# Transmitter.net
KiCad netlist of a schematic drawn in Altium Designer
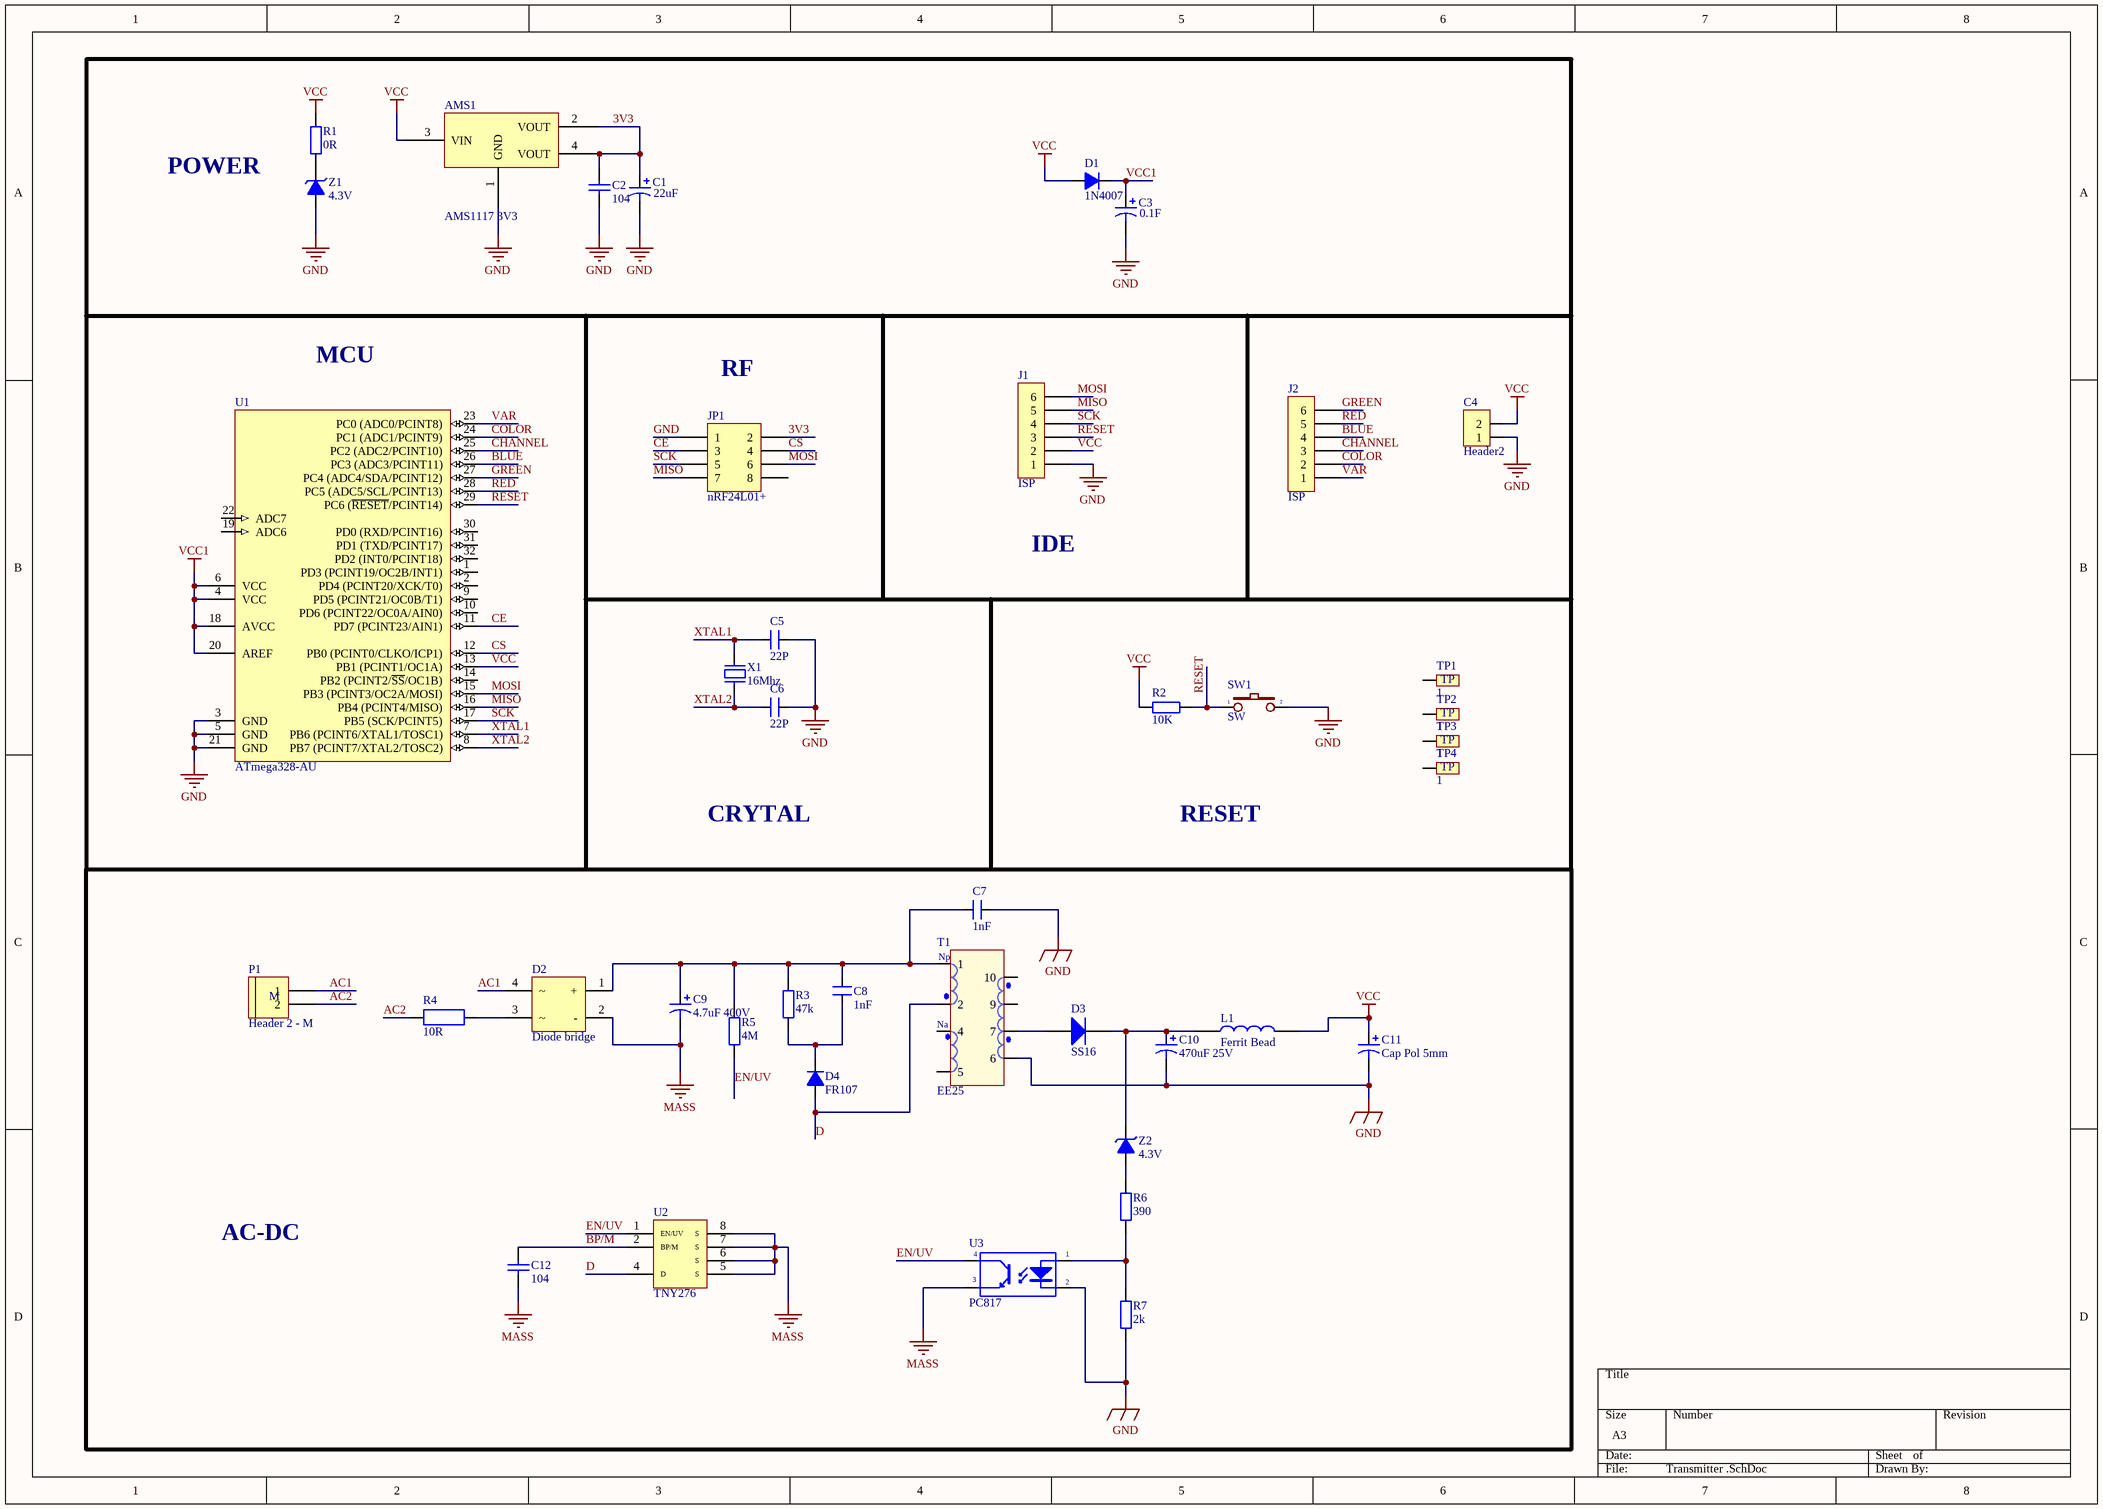
[diagram p0: Transmitter .SchDoc]

(export (version "E")
  (design (tool "Eeschema 10.0.6"))
  (components
    (comp (ref "AMS1")
      (value "AMS1117 3V3")
      (footprint "SOT223-4N")
      (description "AMS")
      (libsource (lib "Thu Vien Chuan") (part "AMS1117"))
    )
    (comp (ref "C1")
      (value "22uF")
      (footprint "C5mm")
      (description "Polarized Capacitor (Axial)")
      (fields (field (name "PUBLISHER") "Altium Limited"))
      (libsource (lib "Thu Vien Chuan") (part "Cap Pol 5mm"))
    )
    (comp (ref "C2")
      (value "104")
      (footprint "Thu Vien Chuan :CN-SMD-0805")
      (libsource (lib "Thu Vien Chuan") (part "CAP 33P_0805"))
    )
    (comp (ref "C3")
      (value "0.1F")
      (footprint "HueNguyenLib:SUP CAP")
      (description "Polarized Capacitor (Axial)")
      (fields (field (name "PUBLISHER") "Altium Limited"))
      (libsource (lib "Thu Vien Chuan") (part "Cap Pol 5mm"))
    )
    (comp (ref "C4")
      (value "Header2")
      (footprint "HDR2")
      (description "Header IDC, 2 x 1 Pin Vertical 2.54mm Pitch (Non-Boxed, Male)")
      (fields
        (field (name "MANUFACTURER") "Würth Elektronik eiSos GmbH")
        (field (name "PARTNO") "613002143121")
        (field (name "CREATED BY") "Karrer Zheng")
      )
      (libsource (lib "Thu Vien Chuan") (part "Header2"))
    )
    (comp (ref "C5")
      (value "22P")
      (footprint "Thu Vien Chuan :CN-SMD-0805")
      (description "Cap np  1pF - 472pF")
      (libsource (lib "Thu Vien Chuan") (part "CN1"))
    )
    (comp (ref "C6")
      (value "22P")
      (footprint "Thu Vien Chuan :CN-SMD-0805")
      (description "Cap np  1pF - 472pF")
      (libsource (lib "Thu Vien Chuan") (part "CN1"))
    )
    (comp (ref "C7")
      (value "1nF")
      (footprint "Thu Vien Chuan :CN4")
      (description "Cap np W0.3")
      (fields (field (name "COPYRIGHT") "VanDungEvn"))
      (libsource (lib "Thu Vien Chuan") (part "CN3"))
    )
    (comp (ref "C8")
      (value "1nF")
      (footprint "CN2")
      (description "Cap np 104 => 105pF")
      (libsource (lib "Thu Vien Chuan") (part "CN2"))
    )
    (comp (ref "C9")
      (value "4.7uF 400V")
      (footprint "C10mm")
      (description "Polarized Capacitor (Axial)")
      (fields (field (name "PUBLISHER") "Altium Limited"))
      (libsource (lib "Thu Vien Chuan") (part "Cap Pol 8mm"))
    )
    (comp (ref "C10")
      (value "470uF 25V")
      (footprint "C10mm")
      (description "Polarized Capacitor (Axial)")
      (fields (field (name "PUBLISHER") "Altium Limited"))
      (libsource (lib "Thu Vien Chuan") (part "Cap Pol 8mm"))
    )
    (comp (ref "C11")
      (value "Cap Pol 5mm")
      (footprint "C5mm")
      (description "Polarized Capacitor (Axial)")
      (fields (field (name "PUBLISHER") "Altium Limited"))
      (libsource (lib "Thu Vien Chuan") (part "Cap Pol 5mm"))
    )
    (comp (ref "C12")
      (value "104")
      (footprint "Thu Vien Chuan :CN-SMD-0805")
      (libsource (lib "Thu Vien Chuan") (part "CAP 33P_0805"))
    )
    (comp (ref "D1")
      (value "1N4007")
      (footprint "D1A")
      (description "Diode 1A")
      (libsource (lib "Thu Vien Chuan") (part "D1A"))
    )
    (comp (ref "D2")
      (value "Diode bridge")
      (footprint "DS207S:DS207S")
      (description "Diode cau 2A 1000V")
      (libsource (lib "DS207S") (part "DS207S"))
    )
    (comp (ref "D3")
      (value "SS16")
      (footprint "HueNguyenLib:SS14")
      (description "Dán")
      (libsource (lib "Altium_Lib_by_KhueNguyenCreator") (part "Diode SS14 ( 1N5819)"))
    )
    (comp (ref "D4")
      (value "FR107")
      (footprint "D1A")
      (description "Diode 1A")
      (libsource (lib "Thu Vien Chuan") (part "D1A"))
    )
    (comp (ref "J1")
      (value "ISP")
      (footprint "Thu Vien Chuan :Header6")
      (description "JUMP DON DUC 2.54")
      (libsource (lib "Thu Vien Chuan") (part "JUMP 6"))
    )
    (comp (ref "J2")
      (value "ISP")
      (footprint "Thu Vien Chuan :Header6")
      (description "JUMP DON DUC 2.54")
      (libsource (lib "Thu Vien Chuan") (part "JUMP 6"))
    )
    (comp (ref "JP1")
      (value "nRF24L01+")
      (footprint "HDR2X4")
      (description "JUMP DOI DUC")
      (fields (field (name "PUBLISHER") "Altium Limited"))
      (libsource (lib "Thu Vien Chuan") (part "JUMP DOI-4"))
    )
    (comp (ref "L1")
      (value "Ferrit Bead")
      (footprint "Cuon Cam:CUON CAM")
      (description "Cuộn lọc RH3.5x9x0.8 Cắm")
      (libsource (lib "Altium_Lib_by_KhueNguyenCreator") (part "CUON CAM 470uH DIP"))
    )
    (comp (ref "P1")
      (value "Header 2 - M")
      (footprint "Medium - Header 2")
      (description "Header, 2-Pin, Medium")
      (fields (field (name "PUBLISHER") "Altium Limited"))
      (libsource (lib "Thu Vien Chuan") (part "Header 2 - M"))
    )
    (comp (ref "R1")
      (value "0R")
      (footprint "Thu Vien Chuan :1206_R")
      (description "Resistor 1/4W")
      (libsource (lib "Thu Vien Chuan") (part "R1/4W"))
    )
    (comp (ref "R2")
      (value "10K")
      (footprint "Thu Vien Chuan :RES-SMD-0805")
      (description "Resistor 1/4W")
      (libsource (lib "Thu Vien Chuan") (part "R1/4W"))
    )
    (comp (ref "R3")
      (value "47k")
      (footprint "Thu Vien Chuan :RES-SMD-0805")
      (description "Resistor 1/4W")
      (libsource (lib "Thu Vien Chuan") (part "R1/4W"))
    )
    (comp (ref "R4")
      (value "10R")
      (footprint "Thu Vien Chuan :RES-1W-LONG")
      (description "Resistor 1W")
      (libsource (lib "Thu Vien Chuan") (part "R1W"))
    )
    (comp (ref "R5")
      (value "4M")
      (footprint "Thu Vien Chuan :RES-SMD-0805")
      (description "Resistor 1/4W")
      (libsource (lib "Thu Vien Chuan") (part "R1/4W"))
    )
    (comp (ref "R6")
      (value "390")
      (footprint "Thu Vien Chuan :RES-SMD-0805")
      (description "Resistor 1/4W")
      (libsource (lib "Thu Vien Chuan") (part "R1/4W"))
    )
    (comp (ref "R7")
      (value "2k")
      (footprint "Thu Vien Chuan :RES-SMD-0805")
      (description "Resistor 1/4W")
      (libsource (lib "Thu Vien Chuan") (part "R1/4W"))
    )
    (comp (ref "SW1")
      (value "SW")
      (footprint "SW2")
      (description "Switch button 2 pin")
      (libsource (lib "Thu Vien Chuan") (part "SW2"))
    )
    (comp (ref "T1")
      (value "EE25")
      (footprint "HueNguyenLib:EE19 5+5")
      (description "EE25 10PIN")
      (libsource (lib "EE25") (part "EE25"))
    )
    (comp (ref "TP1")
      (value "1")
      (footprint "ThePhongLib:Holle 3mm 8mm")
      (description "CONNECT 1")
      (libsource (lib "Thu Vien Chuan MH") (part "TP"))
    )
    (comp (ref "TP2")
      (value "1")
      (footprint "ThePhongLib:Holle 3mm 8mm")
      (description "CONNECT 1")
      (libsource (lib "Thu Vien Chuan MH") (part "TP"))
    )
    (comp (ref "TP3")
      (value "1")
      (footprint "ThePhongLib:Holle 3mm 8mm")
      (description "CONNECT 1")
      (libsource (lib "Thu Vien Chuan MH") (part "TP"))
    )
    (comp (ref "TP4")
      (value "1")
      (footprint "ThePhongLib:Holle 3mm 8mm")
      (description "CONNECT 1")
      (libsource (lib "Thu Vien Chuan MH") (part "TP"))
    )
    (comp (ref "U1")
      (value "ATmega328-AU")
      (footprint "TQFP32")
      (fields (field (name "PUBLISHER") "Altium Limited"))
      (libsource (lib "Thu Vien Chuan") (part "ATmega328-AU"))
    )
    (comp (ref "U2")
      (value "TNY276")
      (footprint "TNY27X DIP:PCBComponent_1")
      (description "TNY274-280\r\nTinySwitch-III Family - DIP/PDIP-8C")
      (libsource (lib "TNY27X-DIP") (part "TNY276"))
    )
    (comp (ref "U3")
      (value "PC817")
      (footprint "DIP4/W0.3")
      (description "Single Opto")
      (libsource (lib "Thu Vien Chuan") (part "PC817"))
    )
    (comp (ref "X1")
      (value "16Mhz")
      (footprint "XT2")
      (description "Crystal For all Crystal 2pin.")
      (libsource (lib "Thu Vien Chuan") (part "XT2"))
    )
    (comp (ref "Z1")
      (value "4.3V")
      (footprint "D1A")
      (description "Diode  Zener")
      (libsource (lib "Thu Vien Chuan") (part "Diode Zener"))
    )
    (comp (ref "Z2")
      (value "4.3V")
      (footprint "D1A")
      (description "Diode  Zener")
      (libsource (lib "Thu Vien Chuan") (part "Diode Zener"))
    )
  )
  (nets
    (net (code "1") (name "/3V3") (class "Default")
      (node (ref "AMS1") (pin "2") (pinfunction "VOUT_2") (pintype "passive"))
      (node (ref "AMS1") (pin "4") (pinfunction "VOUT_4") (pintype "passive"))
      (node (ref "C1") (pin "1") (pinfunction "1_1") (pintype "passive"))
      (node (ref "C2") (pin "2") (pinfunction "2_2") (pintype "passive"))
      (node (ref "JP1") (pin "2") (pinfunction "2_2") (pintype "passive"))
    )
    (net (code "2") (name "/AC1") (class "Default")
      (node (ref "D2") (pin "4") (pinfunction "~_4") (pintype "passive"))
      (node (ref "P1") (pin "1") (pinfunction "1_1") (pintype "passive"))
    )
    (net (code "3") (name "/AC2") (class "Default")
      (node (ref "P1") (pin "2") (pinfunction "2_2") (pintype "passive"))
      (node (ref "R4") (pin "1") (pinfunction "1_1") (pintype "passive"))
    )
    (net (code "4") (name "/BLUE") (class "Default")
      (node (ref "J2") (pin "4") (pinfunction "4_4") (pintype "passive"))
      (node (ref "U1") (pin "26") (pinfunction "PC3_(ADC3/PCINT11)_26") (pintype "bidirectional"))
    )
    (net (code "5") (name "/BP{slash}M") (class "Default")
      (node (ref "C12") (pin "2") (pinfunction "2_2") (pintype "passive"))
      (node (ref "U2") (pin "2") (pinfunction "BP/M_2") (pintype "passive"))
    )
    (net (code "6") (name "/CE") (class "Default")
      (node (ref "JP1") (pin "3") (pinfunction "3_3") (pintype "passive"))
      (node (ref "U1") (pin "11") (pinfunction "PD7_(PCINT23/AIN1)_11") (pintype "bidirectional"))
    )
    (net (code "7") (name "/CHANNEL") (class "Default")
      (node (ref "J2") (pin "3") (pinfunction "3_3") (pintype "passive"))
      (node (ref "U1") (pin "25") (pinfunction "PC2_(ADC2/PCINT10)_25") (pintype "bidirectional"))
    )
    (net (code "8") (name "/COLOR") (class "Default")
      (node (ref "J2") (pin "2") (pinfunction "2_2") (pintype "passive"))
      (node (ref "U1") (pin "24") (pinfunction "PC1_(ADC1/PCINT9)_24") (pintype "bidirectional"))
    )
    (net (code "9") (name "/CS") (class "Default")
      (node (ref "JP1") (pin "4") (pinfunction "4_4") (pintype "passive"))
      (node (ref "U1") (pin "12") (pinfunction "PB0_(PCINT0/CLKO/ICP1)_12") (pintype "bidirectional"))
    )
    (net (code "10") (name "/D") (class "Default")
      (node (ref "D4") (pin "1") (pinfunction "A_1") (pintype "passive"))
      (node (ref "T1") (pin "2") (pinfunction "2_2") (pintype "passive"))
      (node (ref "U2") (pin "4") (pinfunction "D_4") (pintype "passive"))
    )
    (net (code "11") (name "/EN{slash}UV") (class "Default")
      (node (ref "R5") (pin "1") (pinfunction "1_1") (pintype "passive"))
      (node (ref "U2") (pin "1") (pinfunction "EN/UV_1") (pintype "passive"))
      (node (ref "U3") (pin "4") (pinfunction "C_4") (pintype "passive"))
    )
    (net (code "12") (name "/GREEN") (class "Default")
      (node (ref "J2") (pin "6") (pinfunction "6_6") (pintype "passive"))
      (node (ref "U1") (pin "27") (pinfunction "PC4_(ADC4/SDA/PCINT12)_27") (pintype "bidirectional"))
    )
    (net (code "13") (name "/MISO") (class "Default")
      (node (ref "J1") (pin "5") (pinfunction "5_5") (pintype "passive"))
      (node (ref "JP1") (pin "7") (pinfunction "7_7") (pintype "passive"))
      (node (ref "U1") (pin "16") (pinfunction "PB4_(PCINT4/MISO)_16") (pintype "bidirectional"))
    )
    (net (code "14") (name "/MOSI") (class "Default")
      (node (ref "J1") (pin "6") (pinfunction "6_6") (pintype "passive"))
      (node (ref "JP1") (pin "6") (pinfunction "6_6") (pintype "passive"))
      (node (ref "U1") (pin "15") (pinfunction "PB3_(PCINT3/OC2A/MOSI)_15") (pintype "bidirectional"))
    )
    (net (code "15") (name "/RED") (class "Default")
      (node (ref "J2") (pin "5") (pinfunction "5_5") (pintype "passive"))
      (node (ref "U1") (pin "28") (pinfunction "PC5_(ADC5/SCL/PCINT13)_28") (pintype "bidirectional"))
    )
    (net (code "16") (name "/RESET") (class "Default")
      (node (ref "J1") (pin "3") (pinfunction "3_3") (pintype "passive"))
      (node (ref "R2") (pin "2") (pinfunction "2_2") (pintype "passive"))
      (node (ref "SW1") (pin "1") (pinfunction "1_1") (pintype "passive"))
      (node (ref "U1") (pin "29") (pinfunction "PC6_(~{RESET}/PCINT14)_29") (pintype "bidirectional"))
    )
    (net (code "17") (name "/SCK") (class "Default")
      (node (ref "J1") (pin "4") (pinfunction "4_4") (pintype "passive"))
      (node (ref "JP1") (pin "5") (pinfunction "5_5") (pintype "passive"))
      (node (ref "U1") (pin "17") (pinfunction "PB5_(SCK/PCINT5)_17") (pintype "bidirectional"))
    )
    (net (code "18") (name "/VAR") (class "Default")
      (node (ref "J2") (pin "1") (pinfunction "1_1") (pintype "passive"))
      (node (ref "U1") (pin "23") (pinfunction "PC0_(ADC0/PCINT8)_23") (pintype "bidirectional"))
    )
    (net (code "19") (name "/XTAL1") (class "Default")
      (node (ref "C5") (pin "2") (pinfunction "2_2") (pintype "passive"))
      (node (ref "U1") (pin "7") (pinfunction "PB6_(PCINT6/XTAL1/TOSC1)_7") (pintype "bidirectional"))
      (node (ref "X1") (pin "2") (pinfunction "2_2") (pintype "passive"))
    )
    (net (code "20") (name "/XTAL2") (class "Default")
      (node (ref "C6") (pin "2") (pinfunction "2_2") (pintype "passive"))
      (node (ref "U1") (pin "8") (pinfunction "PB7_(PCINT7/XTAL2/TOSC2)_8") (pintype "bidirectional"))
      (node (ref "X1") (pin "1") (pinfunction "1_1") (pintype "passive"))
    )
    (net (code "21") (name "GND") (class "Default")
      (node (ref "AMS1") (pin "1") (pinfunction "GND_1") (pintype "passive"))
      (node (ref "C1") (pin "2") (pinfunction "2_2") (pintype "passive"))
      (node (ref "C10") (pin "2") (pinfunction "2_2") (pintype "passive"))
      (node (ref "C11") (pin "2") (pinfunction "2_2") (pintype "passive"))
      (node (ref "C2") (pin "1") (pinfunction "1_1") (pintype "passive"))
      (node (ref "C3") (pin "2") (pinfunction "2_2") (pintype "passive"))
      (node (ref "C4") (pin "1") (pinfunction "1_1") (pintype "passive"))
      (node (ref "C5") (pin "1") (pinfunction "1_1") (pintype "passive"))
      (node (ref "C6") (pin "1") (pinfunction "1_1") (pintype "passive"))
      (node (ref "C7") (pin "2") (pinfunction "2_2") (pintype "passive"))
      (node (ref "J1") (pin "1") (pinfunction "1_1") (pintype "passive"))
      (node (ref "JP1") (pin "1") (pinfunction "1_1") (pintype "passive"))
      (node (ref "R7") (pin "1") (pinfunction "1_1") (pintype "passive"))
      (node (ref "SW1") (pin "2") (pinfunction "2_2") (pintype "passive"))
      (node (ref "T1") (pin "6") (pinfunction "6_6") (pintype "passive"))
      (node (ref "U1") (pin "21") (pinfunction "GND_21") (pintype "power_in"))
      (node (ref "U1") (pin "3") (pinfunction "GND_3") (pintype "power_in"))
      (node (ref "U1") (pin "5") (pinfunction "GND_5") (pintype "power_in"))
      (node (ref "U3") (pin "2") (pinfunction "K_2") (pintype "passive"))
      (node (ref "Z1") (pin "1") (pinfunction "A_1") (pintype "passive"))
    )
    (net (code "22") (name "MASS") (class "Default")
      (node (ref "C12") (pin "1") (pinfunction "1_1") (pintype "passive"))
      (node (ref "C9") (pin "2") (pinfunction "2_2") (pintype "passive"))
      (node (ref "D2") (pin "2") (pinfunction "-_2") (pintype "passive"))
      (node (ref "U2") (pin "5") (pinfunction "S_5") (pintype "passive"))
      (node (ref "U2") (pin "6") (pinfunction "S_6") (pintype "passive"))
      (node (ref "U2") (pin "7") (pinfunction "S_7") (pintype "passive"))
      (node (ref "U2") (pin "8") (pinfunction "S_8") (pintype "passive"))
      (node (ref "U3") (pin "3") (pinfunction "E_3") (pintype "passive"))
    )
    (net (code "23") (name "Net-(D2-+)") (class "Default")
      (node (ref "C7") (pin "1") (pinfunction "1_1") (pintype "passive"))
      (node (ref "C8") (pin "2") (pinfunction "2_2") (pintype "passive"))
      (node (ref "C9") (pin "1") (pinfunction "1_1") (pintype "passive"))
      (node (ref "D2") (pin "1") (pinfunction "+_1") (pintype "passive"))
      (node (ref "R3") (pin "2") (pinfunction "2_2") (pintype "passive"))
      (node (ref "R5") (pin "2") (pinfunction "2_2") (pintype "passive"))
      (node (ref "T1") (pin "1") (pinfunction "1_1") (pintype "passive"))
    )
    (net (code "24") (name "Net-(D2-~-Pad3)") (class "Default")
      (node (ref "D2") (pin "3") (pinfunction "~_3") (pintype "passive"))
      (node (ref "R4") (pin "2") (pinfunction "2_2") (pintype "passive"))
    )
    (net (code "25") (name "Net-(D3-A)") (class "Default")
      (node (ref "D3") (pin "1") (pinfunction "A_1") (pintype "passive"))
      (node (ref "T1") (pin "7") (pinfunction "7_7") (pintype "passive"))
    )
    (net (code "26") (name "Net-(D3-K)") (class "Default")
      (node (ref "C10") (pin "1") (pinfunction "1_1") (pintype "passive"))
      (node (ref "D3") (pin "2") (pinfunction "K_2") (pintype "passive"))
      (node (ref "L1") (pin "1") (pinfunction "1_1") (pintype "passive"))
      (node (ref "Z2") (pin "2") (pinfunction "K_2") (pintype "passive"))
    )
    (net (code "27") (name "Net-(D4-K)") (class "Default")
      (node (ref "C8") (pin "1") (pinfunction "1_1") (pintype "passive"))
      (node (ref "D4") (pin "2") (pinfunction "K_2") (pintype "passive"))
      (node (ref "R3") (pin "1") (pinfunction "1_1") (pintype "passive"))
    )
    (net (code "28") (name "Net-(U3-A)") (class "Default")
      (node (ref "R6") (pin "1") (pinfunction "1_1") (pintype "passive"))
      (node (ref "R7") (pin "2") (pinfunction "2_2") (pintype "passive"))
      (node (ref "U3") (pin "1") (pinfunction "A_1") (pintype "passive"))
    )
    (net (code "29") (name "Net-(Z1-K)") (class "Default")
      (node (ref "R1") (pin "1") (pinfunction "1_1") (pintype "passive"))
      (node (ref "Z1") (pin "2") (pinfunction "K_2") (pintype "passive"))
    )
    (net (code "30") (name "Net-(Z2-A)") (class "Default")
      (node (ref "R6") (pin "2") (pinfunction "2_2") (pintype "passive"))
      (node (ref "Z2") (pin "1") (pinfunction "A_1") (pintype "passive"))
    )
    (net (code "31") (name "VCC") (class "Default")
      (node (ref "AMS1") (pin "3") (pinfunction "VIN_3") (pintype "passive"))
      (node (ref "C11") (pin "1") (pinfunction "1_1") (pintype "passive"))
      (node (ref "C4") (pin "2") (pinfunction "2_2") (pintype "passive"))
      (node (ref "D1") (pin "1") (pinfunction "A_1") (pintype "passive"))
      (node (ref "J1") (pin "2") (pinfunction "2_2") (pintype "passive"))
      (node (ref "L1") (pin "2") (pinfunction "2_2") (pintype "passive"))
      (node (ref "R1") (pin "2") (pinfunction "2_2") (pintype "passive"))
      (node (ref "R2") (pin "1") (pinfunction "1_1") (pintype "passive"))
      (node (ref "U1") (pin "13") (pinfunction "PB1_(PCINT1/OC1A)_13") (pintype "bidirectional"))
    )
    (net (code "32") (name "VCC1") (class "Default")
      (node (ref "C3") (pin "1") (pinfunction "1_1") (pintype "passive"))
      (node (ref "D1") (pin "2") (pinfunction "K_2") (pintype "passive"))
      (node (ref "U1") (pin "18") (pinfunction "AVCC_18") (pintype "power_in"))
      (node (ref "U1") (pin "20") (pinfunction "AREF_20") (pintype "passive"))
      (node (ref "U1") (pin "4") (pinfunction "VCC_4") (pintype "power_in"))
      (node (ref "U1") (pin "6") (pinfunction "VCC_6") (pintype "power_in"))
    )
    (net (code "33") (name "unconnected-(JP1-Pad8)") (class "Default")
      (node (ref "JP1") (pin "8") (pinfunction "8_8") (pintype "passive"))
    )
    (net (code "34") (name "unconnected-(T1-Pad4)") (class "Default")
      (node (ref "T1") (pin "4") (pinfunction "4_4") (pintype "passive"))
    )
    (net (code "35") (name "unconnected-(T1-Pad5)") (class "Default")
      (node (ref "T1") (pin "5") (pinfunction "5_5") (pintype "passive"))
    )
    (net (code "36") (name "unconnected-(T1-Pad9)") (class "Default")
      (node (ref "T1") (pin "9") (pinfunction "9_9") (pintype "passive"))
    )
    (net (code "37") (name "unconnected-(T1-Pad10)") (class "Default")
      (node (ref "T1") (pin "10") (pinfunction "10_10") (pintype "passive"))
    )
    (net (code "38") (name "unconnected-(TP1-0-PadTP1)") (class "Default")
      (node (ref "TP1") (pin "TP1") (pinfunction "0_TP1") (pintype "passive"))
    )
    (net (code "39") (name "unconnected-(TP2-0-PadTP1)") (class "Default")
      (node (ref "TP2") (pin "TP1") (pinfunction "0_TP1") (pintype "passive"))
    )
    (net (code "40") (name "unconnected-(TP3-0-PadTP1)") (class "Default")
      (node (ref "TP3") (pin "TP1") (pinfunction "0_TP1") (pintype "passive"))
    )
    (net (code "41") (name "unconnected-(TP4-0-PadTP1)") (class "Default")
      (node (ref "TP4") (pin "TP1") (pinfunction "0_TP1") (pintype "passive"))
    )
    (net (code "42") (name "unconnected-(U1-ADC6-Pad19)") (class "Default")
      (node (ref "U1") (pin "19") (pinfunction "ADC6_19") (pintype "input"))
    )
    (net (code "43") (name "unconnected-(U1-ADC7-Pad22)") (class "Default")
      (node (ref "U1") (pin "22") (pinfunction "ADC7_22") (pintype "input"))
    )
    (net (code "44") (name "unconnected-(U1-PB2_(PCINT2{slash}~{SS}{slash}OC1B)-Pad14)") (class "Default")
      (node (ref "U1") (pin "14") (pinfunction "PB2_(PCINT2/~{SS}/OC1B)_14") (pintype "bidirectional"))
    )
    (net (code "45") (name "unconnected-(U1-PD0_(RXD{slash}PCINT16)-Pad30)") (class "Default")
      (node (ref "U1") (pin "30") (pinfunction "PD0_(RXD/PCINT16)_30") (pintype "bidirectional"))
    )
    (net (code "46") (name "unconnected-(U1-PD1_(TXD{slash}PCINT17)-Pad31)") (class "Default")
      (node (ref "U1") (pin "31") (pinfunction "PD1_(TXD/PCINT17)_31") (pintype "bidirectional"))
    )
    (net (code "47") (name "unconnected-(U1-PD2_(INT0{slash}PCINT18)-Pad32)") (class "Default")
      (node (ref "U1") (pin "32") (pinfunction "PD2_(INT0/PCINT18)_32") (pintype "bidirectional"))
    )
    (net (code "48") (name "unconnected-(U1-PD3_(PCINT19{slash}OC2B{slash}INT1)-Pad1)") (class "Default")
      (node (ref "U1") (pin "1") (pinfunction "PD3_(PCINT19/OC2B/INT1)_1") (pintype "bidirectional"))
    )
    (net (code "49") (name "unconnected-(U1-PD4_(PCINT20{slash}XCK{slash}T0)-Pad2)") (class "Default")
      (node (ref "U1") (pin "2") (pinfunction "PD4_(PCINT20/XCK/T0)_2") (pintype "bidirectional"))
    )
    (net (code "50") (name "unconnected-(U1-PD5_(PCINT21{slash}OC0B{slash}T1)-Pad9)") (class "Default")
      (node (ref "U1") (pin "9") (pinfunction "PD5_(PCINT21/OC0B/T1)_9") (pintype "bidirectional"))
    )
    (net (code "51") (name "unconnected-(U1-PD6_(PCINT22{slash}OC0A{slash}AIN0)-Pad10)") (class "Default")
      (node (ref "U1") (pin "10") (pinfunction "PD6_(PCINT22/OC0A/AIN0)_10") (pintype "bidirectional"))
    )
  )
)
